# SCH_BMS.net
KiCad netlist of a schematic drawn in Altium Designer
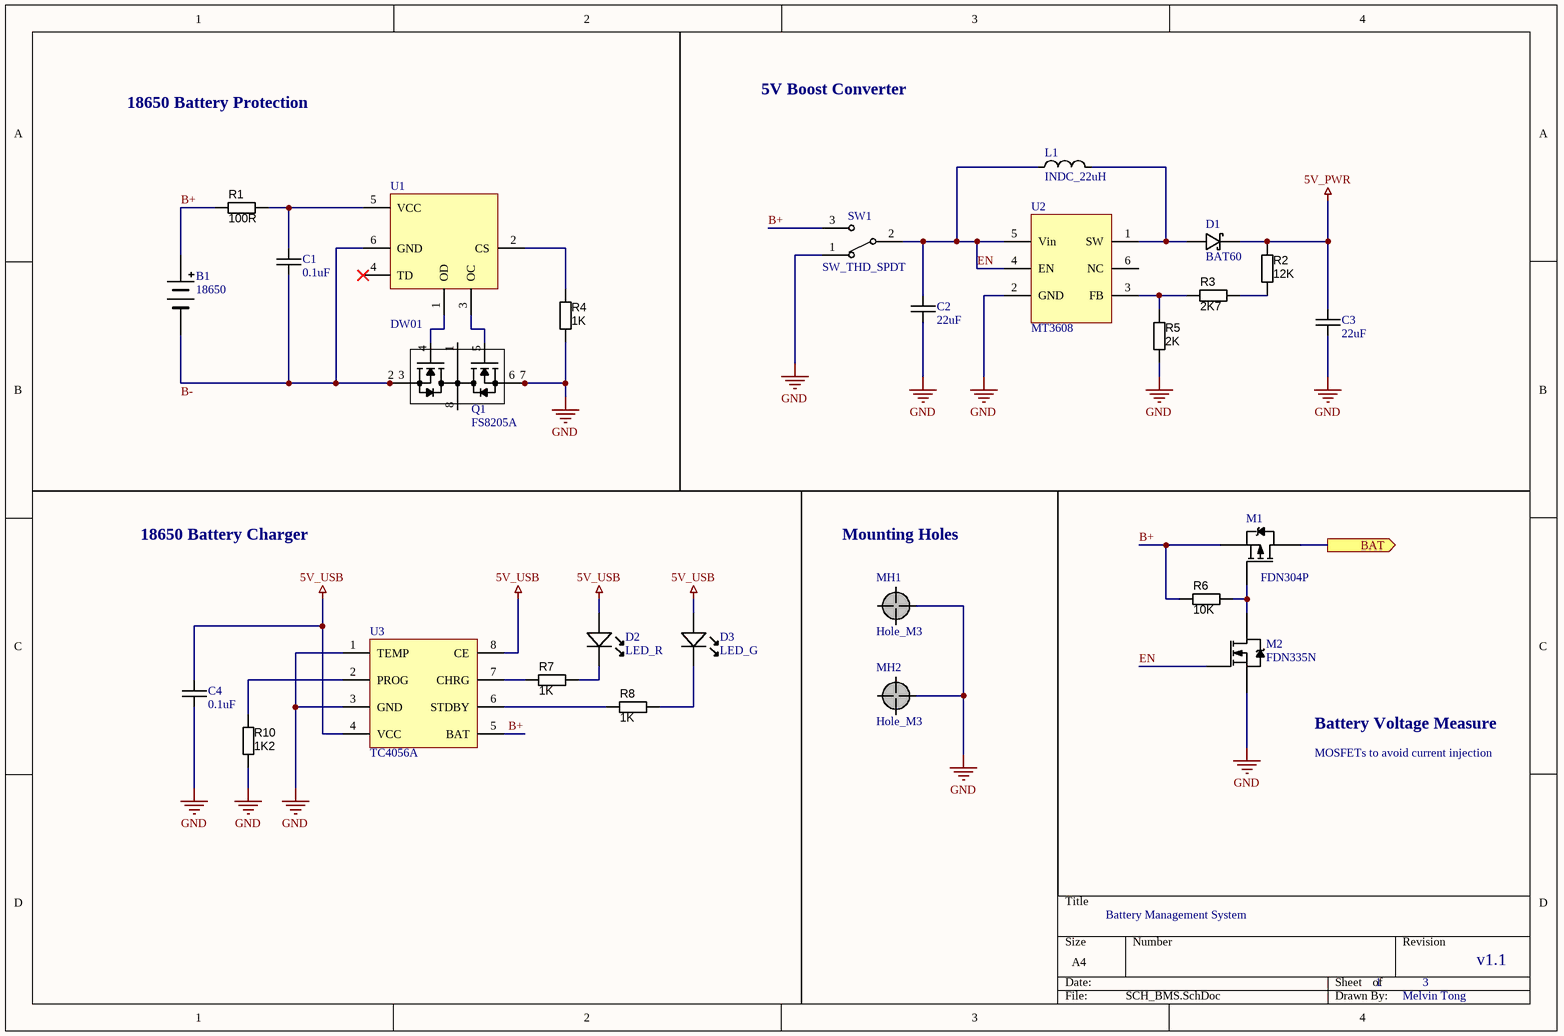
[diagram p0: SCH_BMS.SchDoc]

(export (version "E")
  (design (tool "Eeschema 10.0.6"))
  (components
    (comp (ref "B1")
      (value "18650")
      (footprint "BAT_18650")
      (libsource (lib "SchLib_AirMeter") (part "Battery_18650"))
    )
    (comp (ref "C1")
      (value "0.1uF")
      (footprint "CAP_0805")
      (description "SMD 0805")
      (libsource (lib "SchLib_AirMeter") (part "CAP_0.1uF"))
    )
    (comp (ref "C2")
      (value "22uF")
      (footprint "CAP_1206")
      (description "SMD 1206")
      (libsource (lib "SchLib_AirMeter") (part "CAP_22uF"))
    )
    (comp (ref "C3")
      (value "22uF")
      (footprint "CAP_1206")
      (description "SMD 1206")
      (libsource (lib "SchLib_AirMeter") (part "CAP_22uF"))
    )
    (comp (ref "C4")
      (value "0.1uF")
      (footprint "CAP_0805")
      (description "SMD 0805")
      (libsource (lib "SchLib_AirMeter") (part "CAP_0.1uF"))
    )
    (comp (ref "D1")
      (value "BAT60")
      (footprint "SOD323")
      (description "Schottky Diode 3A, Vf~0.24V, Vr=10V")
      (libsource (lib "SchLib_AirMeter") (part "BAT60"))
    )
    (comp (ref "D2")
      (value "LED_R")
      (footprint "LED_0805")
      (description "SMD_0805 2V")
      (libsource (lib "SchLib_AirMeter") (part "LED_R"))
    )
    (comp (ref "D3")
      (value "LED_G")
      (footprint "LED_0805")
      (description "SMD_0805 3V")
      (libsource (lib "SchLib_AirMeter") (part "LED_G"))
    )
    (comp (ref "L1")
      (value "INDC_22uH")
      (footprint "IND_10x10")
      (libsource (lib "SchLib_AirMeter") (part "INDC_22uH"))
    )
    (comp (ref "M1")
      (value "FDN304P")
      (footprint "SOT23_213")
      (libsource (lib "SchLib_AirMeter") (part "PMOS"))
    )
    (comp (ref "M2")
      (value "FDN335N")
      (footprint "SOT23_213")
      (libsource (lib "SchLib_AirMeter") (part "NMOS"))
    )
    (comp (ref "MH1")
      (value "Hole_M3")
      (footprint "Hole_M3")
      (libsource (lib "SchLib_AirMeter") (part "Hole_M3"))
    )
    (comp (ref "MH2")
      (value "Hole_M3")
      (footprint "Hole_M3")
      (libsource (lib "SchLib_AirMeter") (part "Hole_M3"))
    )
    (comp (ref "Q1")
      (value "FS8205A")
      (footprint "TSSOP65P640X120-8N")
      (description "NMOS, Drain-Connected, Imax 6A")
      (libsource (lib "SchLib_AirMeter") (part "FS8205A"))
    )
    (comp (ref "R1")
      (value "100R")
      (footprint "RESC3216X70N")
      (description "Resistor SMD, 1206")
      (libsource (lib "SchLib_AirMeter") (part "RES_100R"))
    )
    (comp (ref "R2")
      (value "12K")
      (footprint "RESC3216X70N")
      (description "Resistor SMD, 1206")
      (libsource (lib "SchLib_AirMeter") (part "RES_12K"))
    )
    (comp (ref "R3")
      (value "2K7")
      (footprint "RESC3216X70N")
      (description "Resistor SMD, 1206")
      (libsource (lib "SchLib_AirMeter") (part "RES_2K7"))
    )
    (comp (ref "R4")
      (value "1K")
      (footprint "RESC3216X70N")
      (description "Resistor SMD, 1206")
      (libsource (lib "SchLib_AirMeter") (part "RES_1K"))
    )
    (comp (ref "R5")
      (value "2K")
      (footprint "RESC3216X70N")
      (description "Resistor SMD, 1206")
      (libsource (lib "SchLib_AirMeter") (part "RES_2K"))
    )
    (comp (ref "R6")
      (value "10K")
      (footprint "RESC3216X70N")
      (description "Resistor SMD, 1206")
      (libsource (lib "SchLib_AirMeter") (part "RES_10K"))
    )
    (comp (ref "R7")
      (value "1K")
      (footprint "RESC3216X70N")
      (description "Resistor SMD, 1206")
      (libsource (lib "") (part "RES_1K_1"))
    )
    (comp (ref "R8")
      (value "1K")
      (footprint "RESC3216X70N")
      (description "Resistor SMD, 1206")
      (libsource (lib "") (part "RES_1K_1"))
    )
    (comp (ref "R10")
      (value "1K2")
      (footprint "RESC3216X70N")
      (description "Resistor SMD, 1206")
      (libsource (lib "SchLib_AirMeter") (part "RES_1K2"))
    )
    (comp (ref "SW1")
      (value "SW_THD_SPDT")
      (footprint "3P_header")
      (description "Switch 2 position")
      (libsource (lib "SchLib_AirMeter") (part "SW_THD_SPDT"))
    )
    (comp (ref "U1") (value "DW01") (footprint "SOT23-6") (libsource (lib "SchLib_AirMeter") (part "DW01")))
    (comp (ref "U2")
      (value "MT3608")
      (footprint "SOT23-6")
      (description "Boost Converter")
      (libsource (lib "SchLib_AirMeter") (part "MT3608"))
    )
    (comp (ref "U3")
      (value "TC4056A")
      (footprint "SOIC127P600X175-8AN")
      (libsource (lib "SchLib_AirMeter") (part "TC4056A"))
    )
  )
  (nets
    (net (code "1") (name "/B+") (class "Default")
      (node (ref "B1") (pin "1") (pinfunction "B+_1") (pintype "power_in"))
      (node (ref "M1") (pin "2") (pinfunction "S_2") (pintype "passive"))
      (node (ref "R1") (pin "1") (pinfunction "1_1") (pintype "passive"))
      (node (ref "R6") (pin "1") (pinfunction "1_1") (pintype "passive"))
      (node (ref "SW1") (pin "3") (pinfunction "3_3") (pintype "passive"))
      (node (ref "U3") (pin "5") (pinfunction "BAT_5") (pintype "power_in"))
    )
    (net (code "2") (name "/B-") (class "Default")
      (node (ref "B1") (pin "2") (pinfunction "B+_2") (pintype "power_in"))
      (node (ref "C1") (pin "2") (pintype "passive"))
      (node (ref "Q1") (pin "2") (pinfunction "S1_2") (pintype "passive"))
      (node (ref "Q1") (pin "3") (pinfunction "S1_3") (pintype "passive"))
      (node (ref "U1") (pin "6") (pinfunction "GND_6") (pintype "power_in"))
    )
    (net (code "3") (name "/BAT") (class "Default")
      (node (ref "M1") (pin "3") (pinfunction "D_3") (pintype "passive"))
    )
    (net (code "4") (name "/EN") (class "Default")
      (node (ref "C2") (pin "1") (pintype "passive"))
      (node (ref "L1") (pin "1") (pinfunction "1_1") (pintype "passive"))
      (node (ref "M2") (pin "1") (pinfunction "G_1") (pintype "passive"))
      (node (ref "SW1") (pin "2") (pinfunction "2_2") (pintype "passive"))
      (node (ref "U2") (pin "4") (pinfunction "EN_4") (pintype "power_in"))
      (node (ref "U2") (pin "5") (pinfunction "Vin_5") (pintype "power_in"))
    )
    (net (code "5") (name "5V_PWR") (class "Default")
      (node (ref "C3") (pin "1") (pintype "passive"))
      (node (ref "D1") (pin "K") (pinfunction "K_K") (pintype "passive"))
      (node (ref "R2") (pin "1") (pinfunction "1_1") (pintype "passive"))
    )
    (net (code "6") (name "5V_USB") (class "Default")
      (node (ref "C4") (pin "1") (pintype "passive"))
      (node (ref "D2") (pin "A") (pinfunction "A_A") (pintype "passive"))
      (node (ref "D3") (pin "A") (pinfunction "A_A") (pintype "passive"))
      (node (ref "U3") (pin "4") (pinfunction "VCC_4") (pintype "power_in"))
      (node (ref "U3") (pin "8") (pinfunction "CE_8") (pintype "power_in"))
    )
    (net (code "7") (name "GND") (class "Default")
      (node (ref "C2") (pin "2") (pintype "passive"))
      (node (ref "C3") (pin "2") (pintype "passive"))
      (node (ref "C4") (pin "2") (pintype "passive"))
      (node (ref "M2") (pin "2") (pinfunction "S_2") (pintype "passive"))
      (node (ref "MH1") (pin "MH") (pinfunction "MH_MH") (pintype "passive"))
      (node (ref "MH2") (pin "MH") (pinfunction "MH_MH") (pintype "passive"))
      (node (ref "Q1") (pin "6") (pinfunction "S1_6") (pintype "passive"))
      (node (ref "Q1") (pin "7") (pinfunction "S1_7") (pintype "passive"))
      (node (ref "R10") (pin "2") (pinfunction "2_2") (pintype "passive"))
      (node (ref "R4") (pin "2") (pinfunction "2_2") (pintype "passive"))
      (node (ref "R5") (pin "1") (pinfunction "1_1") (pintype "passive"))
      (node (ref "SW1") (pin "1") (pinfunction "1_1") (pintype "passive"))
      (node (ref "U2") (pin "2") (pinfunction "GND_2") (pintype "power_in"))
      (node (ref "U3") (pin "1") (pinfunction "TEMP_1") (pintype "power_in"))
      (node (ref "U3") (pin "3") (pinfunction "GND_3") (pintype "power_in"))
    )
    (net (code "8") (name "Net-(D2-PadK)") (class "Default")
      (node (ref "D2") (pin "K") (pinfunction "K_K") (pintype "passive"))
      (node (ref "R7") (pin "2") (pinfunction "2_2") (pintype "passive"))
    )
    (net (code "9") (name "Net-(D3-PadK)") (class "Default")
      (node (ref "D3") (pin "K") (pinfunction "K_K") (pintype "passive"))
      (node (ref "R8") (pin "2") (pinfunction "2_2") (pintype "passive"))
    )
    (net (code "10") (name "Net-(M1-G)") (class "Default")
      (node (ref "M1") (pin "1") (pinfunction "G_1") (pintype "passive"))
      (node (ref "M2") (pin "3") (pinfunction "D_3") (pintype "passive"))
      (node (ref "R6") (pin "2") (pinfunction "2_2") (pintype "passive"))
    )
    (net (code "11") (name "Net-(Q1-G1)") (class "Default")
      (node (ref "Q1") (pin "4") (pinfunction "G1_4") (pintype "passive"))
      (node (ref "U1") (pin "1") (pinfunction "OD_1") (pintype "power_in"))
    )
    (net (code "12") (name "Net-(Q1-G2)") (class "Default")
      (node (ref "Q1") (pin "5") (pinfunction "G2_5") (pintype "passive"))
      (node (ref "U1") (pin "3") (pinfunction "OC_3") (pintype "power_in"))
    )
    (net (code "13") (name "Net-(R2-Pad2)") (class "Default")
      (node (ref "R2") (pin "2") (pinfunction "2_2") (pintype "passive"))
      (node (ref "R3") (pin "2") (pinfunction "2_2") (pintype "passive"))
    )
    (net (code "14") (name "Net-(U1-CS)") (class "Default")
      (node (ref "R4") (pin "1") (pinfunction "1_1") (pintype "passive"))
      (node (ref "U1") (pin "2") (pinfunction "CS_2") (pintype "power_in"))
    )
    (net (code "15") (name "Net-(U1-VCC)") (class "Default")
      (node (ref "C1") (pin "1") (pintype "passive"))
      (node (ref "R1") (pin "2") (pinfunction "2_2") (pintype "passive"))
      (node (ref "U1") (pin "5") (pinfunction "VCC_5") (pintype "power_in"))
    )
    (net (code "16") (name "Net-(U2-FB)") (class "Default")
      (node (ref "R3") (pin "1") (pinfunction "1_1") (pintype "passive"))
      (node (ref "R5") (pin "2") (pinfunction "2_2") (pintype "passive"))
      (node (ref "U2") (pin "3") (pinfunction "FB_3") (pintype "power_in"))
    )
    (net (code "17") (name "Net-(U2-SW)") (class "Default")
      (node (ref "D1") (pin "A") (pinfunction "A_A") (pintype "passive"))
      (node (ref "L1") (pin "2") (pinfunction "2_2") (pintype "passive"))
      (node (ref "U2") (pin "1") (pinfunction "SW_1") (pintype "power_in"))
    )
    (net (code "18") (name "Net-(U3-CHRG)") (class "Default")
      (node (ref "R7") (pin "1") (pinfunction "1_1") (pintype "passive"))
      (node (ref "U3") (pin "7") (pinfunction "CHRG_7") (pintype "power_in"))
    )
    (net (code "19") (name "Net-(U3-PROG)") (class "Default")
      (node (ref "R10") (pin "1") (pinfunction "1_1") (pintype "passive"))
      (node (ref "U3") (pin "2") (pinfunction "PROG_2") (pintype "passive"))
    )
    (net (code "20") (name "Net-(U3-STDBY)") (class "Default")
      (node (ref "R8") (pin "1") (pinfunction "1_1") (pintype "passive"))
      (node (ref "U3") (pin "6") (pinfunction "STDBY_6") (pintype "power_in"))
    )
    (net (code "21") (name "unconnected-(Q1-D12-Pad1)") (class "Default")
      (node (ref "Q1") (pin "1") (pinfunction "D12_1") (pintype "passive"))
    )
    (net (code "22") (name "unconnected-(Q1-D12-Pad8)") (class "Default")
      (node (ref "Q1") (pin "8") (pinfunction "D12_8") (pintype "passive"))
    )
    (net (code "23") (name "unconnected-(U1-TD-Pad4)") (class "Default")
      (node (ref "U1") (pin "4") (pinfunction "TD_4") (pintype "power_in+no_connect"))
    )
    (net (code "24") (name "unconnected-(U2-NC-Pad6)") (class "Default")
      (node (ref "U2") (pin "6") (pinfunction "NC_6") (pintype "power_in"))
    )
  )
)
